# Main.net
KiCad netlist of a schematic drawn in Altium Designer
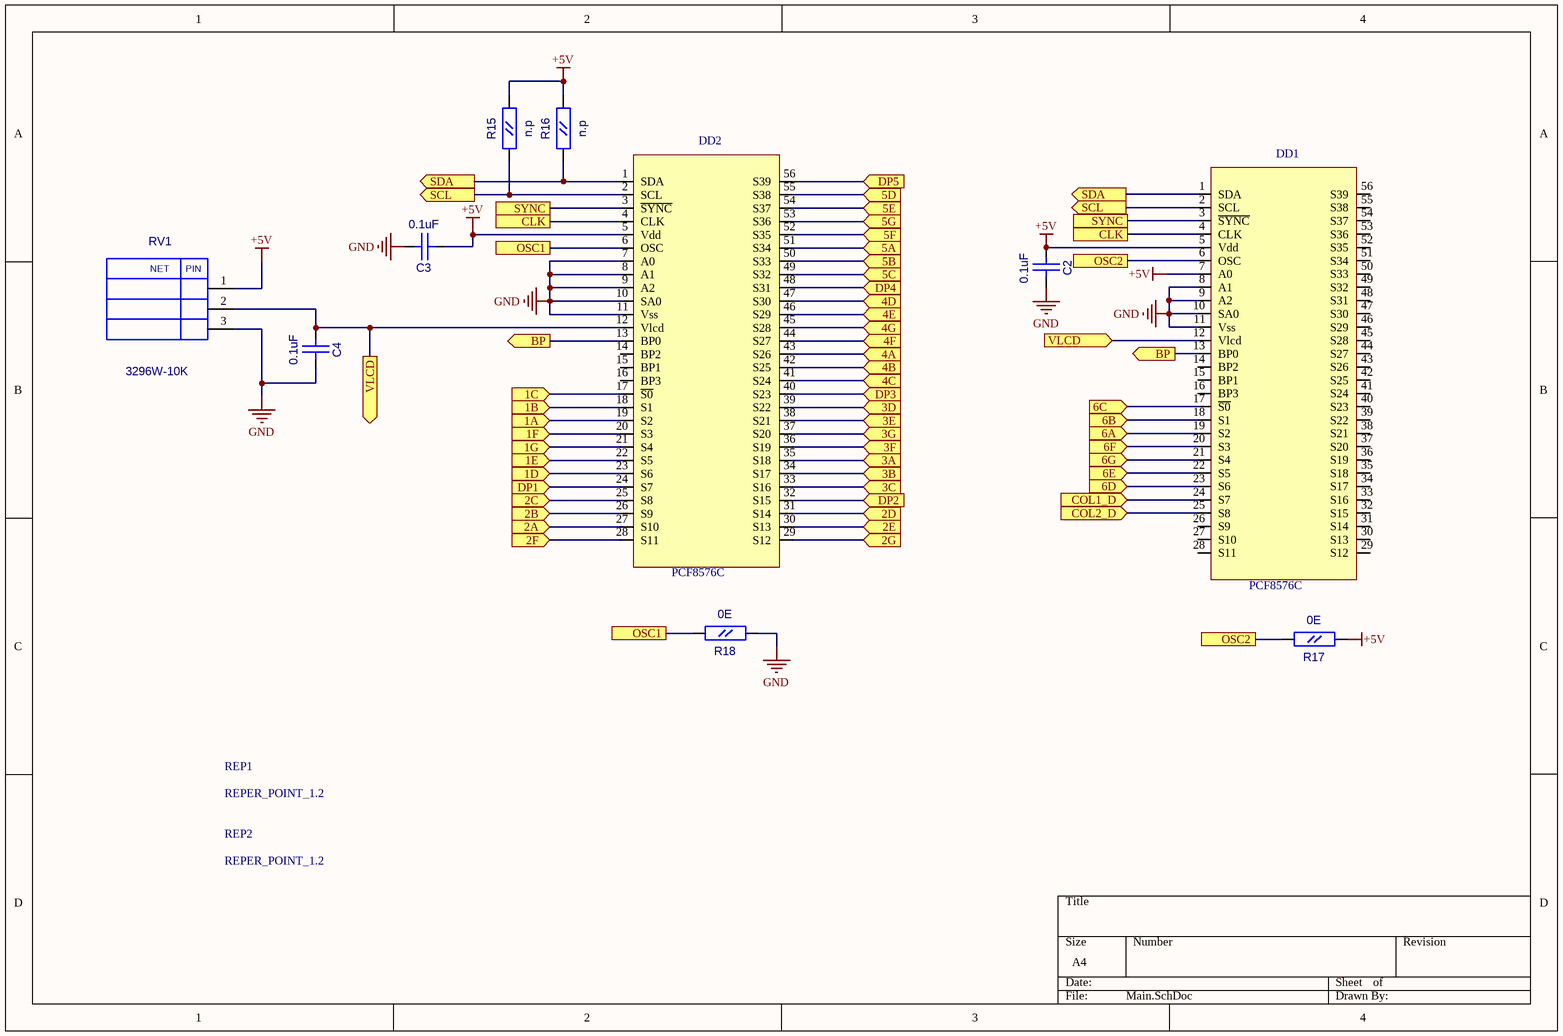
[diagram p0: Main.SchDoc]

(export (version "E")
  (design (tool "Eeschema 10.0.6"))
  (components
    (comp (ref "C2")
      (value "0.1uF")
      (footprint "CC0603")
      (description "CC0603")
      (libsource (lib "gprs_modem_2") (part "CC0603"))
    )
    (comp (ref "C3")
      (value "0.1uF")
      (footprint "CC0603")
      (description "CC0603")
      (libsource (lib "gprs_modem_2") (part "CC0603"))
    )
    (comp (ref "C4")
      (value "0.1uF")
      (footprint "CC0603")
      (description "CC0603")
      (libsource (lib "gprs_modem_2") (part "CC0603"))
    )
    (comp (ref "DD1")
      (value "PCF8576C")
      (footprint "SOT190-1")
      (description "LCD Controller")
      (libsource (lib "gprs_modem_2") (part "PCF8576"))
    )
    (comp (ref "DD2")
      (value "PCF8576C")
      (footprint "SOT190-1")
      (description "LCD Controller")
      (libsource (lib "gprs_modem_2") (part "PCF8576"))
    )
    (comp (ref "R15")
      (value "n.p")
      (footprint "RC0603")
      (description "RC0603")
      (libsource (lib "gprs_modem_2") (part "RC0603"))
    )
    (comp (ref "R16")
      (value "n.p")
      (footprint "RC0603")
      (description "RC0603")
      (libsource (lib "gprs_modem_2") (part "RC0603"))
    )
    (comp (ref "R17")
      (value "0E")
      (footprint "RC0603")
      (description "RC0603")
      (libsource (lib "gprs_modem_2") (part "RC0603"))
    )
    (comp (ref "R18")
      (value "0E")
      (footprint "RC0603")
      (description "RC0603")
      (libsource (lib "gprs_modem_2") (part "RC0603"))
    )
    (comp (ref "REP1")
      (value "REPER_POINT_1.2")
      (footprint "REPER1.2")
      (description "REPER1.2")
      (libsource (lib "gprs_modem_2") (part "REPER1.2"))
    )
    (comp (ref "REP2")
      (value "REPER_POINT_1.2")
      (footprint "REPER1.2")
      (description "REPER1.2")
      (libsource (lib "gprs_modem_2") (part "REPER1.2"))
    )
    (comp (ref "RV1")
      (value "3296W-10K")
      (footprint "PLS-03")
      (libsource (lib "gprs_modem_2") (part "PLS03"))
    )
  )
  (nets
    (net (code "1") (name "+5V") (class "Default")
      (node (ref "C2") (pin "1") (pinfunction "A_1") (pintype "passive"))
      (node (ref "C3") (pin "1") (pinfunction "A_1") (pintype "passive"))
      (node (ref "DD1") (pin "5") (pinfunction "Vdd_5") (pintype "passive"))
      (node (ref "DD1") (pin "7") (pinfunction "A0_7") (pintype "passive"))
      (node (ref "DD2") (pin "5") (pinfunction "Vdd_5") (pintype "passive"))
      (node (ref "R15") (pin "2") (pinfunction "B_2") (pintype "passive"))
      (node (ref "R16") (pin "2") (pinfunction "B_2") (pintype "passive"))
      (node (ref "R17") (pin "1") (pinfunction "A_1") (pintype "passive"))
      (node (ref "RV1") (pin "1") (pinfunction "1_1") (pintype "passive"))
    )
    (net (code "2") (name "/1A") (class "Default")
      (node (ref "DD2") (pin "19") (pinfunction "S2_19") (pintype "passive"))
    )
    (net (code "3") (name "/1B") (class "Default")
      (node (ref "DD2") (pin "18") (pinfunction "S1_18") (pintype "passive"))
    )
    (net (code "4") (name "/1C") (class "Default")
      (node (ref "DD2") (pin "17") (pinfunction "S0_17") (pintype "passive"))
    )
    (net (code "5") (name "/1D") (class "Default")
      (node (ref "DD2") (pin "23") (pinfunction "S6_23") (pintype "passive"))
    )
    (net (code "6") (name "/1E") (class "Default")
      (node (ref "DD2") (pin "22") (pinfunction "S5_22") (pintype "passive"))
    )
    (net (code "7") (name "/1F") (class "Default")
      (node (ref "DD2") (pin "20") (pinfunction "S3_20") (pintype "passive"))
    )
    (net (code "8") (name "/1G") (class "Default")
      (node (ref "DD2") (pin "21") (pinfunction "S4_21") (pintype "passive"))
    )
    (net (code "9") (name "/2A") (class "Default")
      (node (ref "DD2") (pin "27") (pinfunction "S10_27") (pintype "passive"))
    )
    (net (code "10") (name "/2B") (class "Default")
      (node (ref "DD2") (pin "26") (pinfunction "S9_26") (pintype "passive"))
    )
    (net (code "11") (name "/2C") (class "Default")
      (node (ref "DD2") (pin "25") (pinfunction "S8_25") (pintype "passive"))
    )
    (net (code "12") (name "/2D") (class "Default")
      (node (ref "DD2") (pin "31") (pinfunction "S14_31") (pintype "passive"))
    )
    (net (code "13") (name "/2E") (class "Default")
      (node (ref "DD2") (pin "30") (pinfunction "S13_30") (pintype "passive"))
    )
    (net (code "14") (name "/2F") (class "Default")
      (node (ref "DD2") (pin "28") (pinfunction "S11_28") (pintype "passive"))
    )
    (net (code "15") (name "/2G") (class "Default")
      (node (ref "DD2") (pin "29") (pinfunction "S12_29") (pintype "passive"))
    )
    (net (code "16") (name "/3A") (class "Default")
      (node (ref "DD2") (pin "35") (pinfunction "S18_35") (pintype "passive"))
    )
    (net (code "17") (name "/3B") (class "Default")
      (node (ref "DD2") (pin "34") (pinfunction "S17_34") (pintype "passive"))
    )
    (net (code "18") (name "/3C") (class "Default")
      (node (ref "DD2") (pin "33") (pinfunction "S16_33") (pintype "passive"))
    )
    (net (code "19") (name "/3D") (class "Default")
      (node (ref "DD2") (pin "39") (pinfunction "S22_39") (pintype "passive"))
    )
    (net (code "20") (name "/3E") (class "Default")
      (node (ref "DD2") (pin "38") (pinfunction "S21_38") (pintype "passive"))
    )
    (net (code "21") (name "/3F") (class "Default")
      (node (ref "DD2") (pin "36") (pinfunction "S19_36") (pintype "passive"))
    )
    (net (code "22") (name "/3G") (class "Default")
      (node (ref "DD2") (pin "37") (pinfunction "S20_37") (pintype "passive"))
    )
    (net (code "23") (name "/4A") (class "Default")
      (node (ref "DD2") (pin "43") (pinfunction "S26_43") (pintype "passive"))
    )
    (net (code "24") (name "/4B") (class "Default")
      (node (ref "DD2") (pin "42") (pinfunction "S25_42") (pintype "passive"))
    )
    (net (code "25") (name "/4C") (class "Default")
      (node (ref "DD2") (pin "41") (pinfunction "S24_41") (pintype "passive"))
    )
    (net (code "26") (name "/4D") (class "Default")
      (node (ref "DD2") (pin "47") (pinfunction "S30_47") (pintype "passive"))
    )
    (net (code "27") (name "/4E") (class "Default")
      (node (ref "DD2") (pin "46") (pinfunction "S29_46") (pintype "passive"))
    )
    (net (code "28") (name "/4F") (class "Default")
      (node (ref "DD2") (pin "44") (pinfunction "S27_44") (pintype "passive"))
    )
    (net (code "29") (name "/4G") (class "Default")
      (node (ref "DD2") (pin "45") (pinfunction "S28_45") (pintype "passive"))
    )
    (net (code "30") (name "/5A") (class "Default")
      (node (ref "DD2") (pin "51") (pinfunction "S34_51") (pintype "passive"))
    )
    (net (code "31") (name "/5B") (class "Default")
      (node (ref "DD2") (pin "50") (pinfunction "S33_50") (pintype "passive"))
    )
    (net (code "32") (name "/5C") (class "Default")
      (node (ref "DD2") (pin "49") (pinfunction "S32_49") (pintype "passive"))
    )
    (net (code "33") (name "/5D") (class "Default")
      (node (ref "DD2") (pin "55") (pinfunction "S38_55") (pintype "passive"))
    )
    (net (code "34") (name "/5E") (class "Default")
      (node (ref "DD2") (pin "54") (pinfunction "S37_54") (pintype "passive"))
    )
    (net (code "35") (name "/5F") (class "Default")
      (node (ref "DD2") (pin "52") (pinfunction "S35_52") (pintype "passive"))
    )
    (net (code "36") (name "/5G") (class "Default")
      (node (ref "DD2") (pin "53") (pinfunction "S36_53") (pintype "passive"))
    )
    (net (code "37") (name "/6A") (class "Default")
      (node (ref "DD1") (pin "19") (pinfunction "S2_19") (pintype "passive"))
    )
    (net (code "38") (name "/6B") (class "Default")
      (node (ref "DD1") (pin "18") (pinfunction "S1_18") (pintype "passive"))
    )
    (net (code "39") (name "/6C") (class "Default")
      (node (ref "DD1") (pin "17") (pinfunction "S0_17") (pintype "passive"))
    )
    (net (code "40") (name "/6D") (class "Default")
      (node (ref "DD1") (pin "23") (pinfunction "S6_23") (pintype "passive"))
    )
    (net (code "41") (name "/6E") (class "Default")
      (node (ref "DD1") (pin "22") (pinfunction "S5_22") (pintype "passive"))
    )
    (net (code "42") (name "/6F") (class "Default")
      (node (ref "DD1") (pin "20") (pinfunction "S3_20") (pintype "passive"))
    )
    (net (code "43") (name "/6G") (class "Default")
      (node (ref "DD1") (pin "21") (pinfunction "S4_21") (pintype "passive"))
    )
    (net (code "44") (name "/BP") (class "Default")
      (node (ref "DD1") (pin "13") (pinfunction "BP0_13") (pintype "passive"))
      (node (ref "DD2") (pin "13") (pinfunction "BP0_13") (pintype "passive"))
    )
    (net (code "45") (name "/CLK") (class "Default")
      (node (ref "DD1") (pin "4") (pinfunction "CLK_4") (pintype "passive"))
      (node (ref "DD2") (pin "4") (pinfunction "CLK_4") (pintype "passive"))
    )
    (net (code "46") (name "/COL1_D") (class "Default")
      (node (ref "DD1") (pin "24") (pinfunction "S7_24") (pintype "passive"))
    )
    (net (code "47") (name "/COL2_D") (class "Default")
      (node (ref "DD1") (pin "25") (pinfunction "S8_25") (pintype "passive"))
    )
    (net (code "48") (name "/DP1") (class "Default")
      (node (ref "DD2") (pin "24") (pinfunction "S7_24") (pintype "passive"))
    )
    (net (code "49") (name "/DP2") (class "Default")
      (node (ref "DD2") (pin "32") (pinfunction "S15_32") (pintype "passive"))
    )
    (net (code "50") (name "/DP3") (class "Default")
      (node (ref "DD2") (pin "40") (pinfunction "S23_40") (pintype "passive"))
    )
    (net (code "51") (name "/DP4") (class "Default")
      (node (ref "DD2") (pin "48") (pinfunction "S31_48") (pintype "passive"))
    )
    (net (code "52") (name "/DP5") (class "Default")
      (node (ref "DD2") (pin "56") (pinfunction "S39_56") (pintype "passive"))
    )
    (net (code "53") (name "/OSC1") (class "Default")
      (node (ref "DD2") (pin "6") (pinfunction "OSC_6") (pintype "passive"))
      (node (ref "R18") (pin "2") (pinfunction "B_2") (pintype "passive"))
    )
    (net (code "54") (name "/OSC2") (class "Default")
      (node (ref "DD1") (pin "6") (pinfunction "OSC_6") (pintype "passive"))
      (node (ref "R17") (pin "2") (pinfunction "B_2") (pintype "passive"))
    )
    (net (code "55") (name "/SCL") (class "Default")
      (node (ref "DD1") (pin "2") (pinfunction "SCL_2") (pintype "passive"))
      (node (ref "DD2") (pin "2") (pinfunction "SCL_2") (pintype "passive"))
      (node (ref "R15") (pin "1") (pinfunction "A_1") (pintype "passive"))
    )
    (net (code "56") (name "/SDA") (class "Default")
      (node (ref "DD1") (pin "1") (pinfunction "SDA_1") (pintype "passive"))
      (node (ref "DD2") (pin "1") (pinfunction "SDA_1") (pintype "passive"))
      (node (ref "R16") (pin "1") (pinfunction "A_1") (pintype "passive"))
    )
    (net (code "57") (name "/SYNC") (class "Default")
      (node (ref "DD1") (pin "3") (pinfunction "~{SYNC}_3") (pintype "passive"))
      (node (ref "DD2") (pin "3") (pinfunction "~{SYNC}_3") (pintype "passive"))
    )
    (net (code "58") (name "/VLCD") (class "Default")
      (node (ref "C4") (pin "1") (pinfunction "A_1") (pintype "passive"))
      (node (ref "DD1") (pin "12") (pinfunction "Vlcd_12") (pintype "passive"))
      (node (ref "DD2") (pin "12") (pinfunction "Vlcd_12") (pintype "passive"))
      (node (ref "RV1") (pin "2") (pinfunction "2_2") (pintype "passive"))
    )
    (net (code "59") (name "GND") (class "Default")
      (node (ref "C2") (pin "2") (pinfunction "B_2") (pintype "passive"))
      (node (ref "C3") (pin "2") (pinfunction "B_2") (pintype "passive"))
      (node (ref "C4") (pin "2") (pinfunction "B_2") (pintype "passive"))
      (node (ref "DD1") (pin "10") (pinfunction "SA0_10") (pintype "passive"))
      (node (ref "DD1") (pin "11") (pinfunction "Vss_11") (pintype "passive"))
      (node (ref "DD1") (pin "8") (pinfunction "A1_8") (pintype "passive"))
      (node (ref "DD1") (pin "9") (pinfunction "A2_9") (pintype "passive"))
      (node (ref "DD2") (pin "10") (pinfunction "SA0_10") (pintype "passive"))
      (node (ref "DD2") (pin "11") (pinfunction "Vss_11") (pintype "passive"))
      (node (ref "DD2") (pin "7") (pinfunction "A0_7") (pintype "passive"))
      (node (ref "DD2") (pin "8") (pinfunction "A1_8") (pintype "passive"))
      (node (ref "DD2") (pin "9") (pinfunction "A2_9") (pintype "passive"))
      (node (ref "R18") (pin "1") (pinfunction "A_1") (pintype "passive"))
      (node (ref "RV1") (pin "3") (pinfunction "3_3") (pintype "passive"))
    )
    (net (code "60") (name "unconnected-(DD1-BP1-Pad15)") (class "Default")
      (node (ref "DD1") (pin "15") (pinfunction "BP1_15") (pintype "passive"))
    )
    (net (code "61") (name "unconnected-(DD1-BP2-Pad14)") (class "Default")
      (node (ref "DD1") (pin "14") (pinfunction "BP2_14") (pintype "passive"))
    )
    (net (code "62") (name "unconnected-(DD1-BP3-Pad16)") (class "Default")
      (node (ref "DD1") (pin "16") (pinfunction "BP3_16") (pintype "passive"))
    )
    (net (code "63") (name "unconnected-(DD1-S9-Pad26)") (class "Default")
      (node (ref "DD1") (pin "26") (pinfunction "S9_26") (pintype "passive"))
    )
    (net (code "64") (name "unconnected-(DD1-S10-Pad27)") (class "Default")
      (node (ref "DD1") (pin "27") (pinfunction "S10_27") (pintype "passive"))
    )
    (net (code "65") (name "unconnected-(DD1-S11-Pad28)") (class "Default")
      (node (ref "DD1") (pin "28") (pinfunction "S11_28") (pintype "passive"))
    )
    (net (code "66") (name "unconnected-(DD1-S12-Pad29)") (class "Default")
      (node (ref "DD1") (pin "29") (pinfunction "S12_29") (pintype "passive"))
    )
    (net (code "67") (name "unconnected-(DD1-S13-Pad30)") (class "Default")
      (node (ref "DD1") (pin "30") (pinfunction "S13_30") (pintype "passive"))
    )
    (net (code "68") (name "unconnected-(DD1-S14-Pad31)") (class "Default")
      (node (ref "DD1") (pin "31") (pinfunction "S14_31") (pintype "passive"))
    )
    (net (code "69") (name "unconnected-(DD1-S15-Pad32)") (class "Default")
      (node (ref "DD1") (pin "32") (pinfunction "S15_32") (pintype "passive"))
    )
    (net (code "70") (name "unconnected-(DD1-S16-Pad33)") (class "Default")
      (node (ref "DD1") (pin "33") (pinfunction "S16_33") (pintype "passive"))
    )
    (net (code "71") (name "unconnected-(DD1-S17-Pad34)") (class "Default")
      (node (ref "DD1") (pin "34") (pinfunction "S17_34") (pintype "passive"))
    )
    (net (code "72") (name "unconnected-(DD1-S18-Pad35)") (class "Default")
      (node (ref "DD1") (pin "35") (pinfunction "S18_35") (pintype "passive"))
    )
    (net (code "73") (name "unconnected-(DD1-S19-Pad36)") (class "Default")
      (node (ref "DD1") (pin "36") (pinfunction "S19_36") (pintype "passive"))
    )
    (net (code "74") (name "unconnected-(DD1-S20-Pad37)") (class "Default")
      (node (ref "DD1") (pin "37") (pinfunction "S20_37") (pintype "passive"))
    )
    (net (code "75") (name "unconnected-(DD1-S21-Pad38)") (class "Default")
      (node (ref "DD1") (pin "38") (pinfunction "S21_38") (pintype "passive"))
    )
    (net (code "76") (name "unconnected-(DD1-S22-Pad39)") (class "Default")
      (node (ref "DD1") (pin "39") (pinfunction "S22_39") (pintype "passive"))
    )
    (net (code "77") (name "unconnected-(DD1-S23-Pad40)") (class "Default")
      (node (ref "DD1") (pin "40") (pinfunction "S23_40") (pintype "passive"))
    )
    (net (code "78") (name "unconnected-(DD1-S24-Pad41)") (class "Default")
      (node (ref "DD1") (pin "41") (pinfunction "S24_41") (pintype "passive"))
    )
    (net (code "79") (name "unconnected-(DD1-S25-Pad42)") (class "Default")
      (node (ref "DD1") (pin "42") (pinfunction "S25_42") (pintype "passive"))
    )
    (net (code "80") (name "unconnected-(DD1-S26-Pad43)") (class "Default")
      (node (ref "DD1") (pin "43") (pinfunction "S26_43") (pintype "passive"))
    )
    (net (code "81") (name "unconnected-(DD1-S27-Pad44)") (class "Default")
      (node (ref "DD1") (pin "44") (pinfunction "S27_44") (pintype "passive"))
    )
    (net (code "82") (name "unconnected-(DD1-S28-Pad45)") (class "Default")
      (node (ref "DD1") (pin "45") (pinfunction "S28_45") (pintype "passive"))
    )
    (net (code "83") (name "unconnected-(DD1-S29-Pad46)") (class "Default")
      (node (ref "DD1") (pin "46") (pinfunction "S29_46") (pintype "passive"))
    )
    (net (code "84") (name "unconnected-(DD1-S30-Pad47)") (class "Default")
      (node (ref "DD1") (pin "47") (pinfunction "S30_47") (pintype "passive"))
    )
    (net (code "85") (name "unconnected-(DD1-S31-Pad48)") (class "Default")
      (node (ref "DD1") (pin "48") (pinfunction "S31_48") (pintype "passive"))
    )
    (net (code "86") (name "unconnected-(DD1-S32-Pad49)") (class "Default")
      (node (ref "DD1") (pin "49") (pinfunction "S32_49") (pintype "passive"))
    )
    (net (code "87") (name "unconnected-(DD1-S33-Pad50)") (class "Default")
      (node (ref "DD1") (pin "50") (pinfunction "S33_50") (pintype "passive"))
    )
    (net (code "88") (name "unconnected-(DD1-S34-Pad51)") (class "Default")
      (node (ref "DD1") (pin "51") (pinfunction "S34_51") (pintype "passive"))
    )
    (net (code "89") (name "unconnected-(DD1-S35-Pad52)") (class "Default")
      (node (ref "DD1") (pin "52") (pinfunction "S35_52") (pintype "passive"))
    )
    (net (code "90") (name "unconnected-(DD1-S36-Pad53)") (class "Default")
      (node (ref "DD1") (pin "53") (pinfunction "S36_53") (pintype "passive"))
    )
    (net (code "91") (name "unconnected-(DD1-S37-Pad54)") (class "Default")
      (node (ref "DD1") (pin "54") (pinfunction "S37_54") (pintype "passive"))
    )
    (net (code "92") (name "unconnected-(DD1-S38-Pad55)") (class "Default")
      (node (ref "DD1") (pin "55") (pinfunction "S38_55") (pintype "passive"))
    )
    (net (code "93") (name "unconnected-(DD1-S39-Pad56)") (class "Default")
      (node (ref "DD1") (pin "56") (pinfunction "S39_56") (pintype "passive"))
    )
    (net (code "94") (name "unconnected-(DD2-BP1-Pad15)") (class "Default")
      (node (ref "DD2") (pin "15") (pinfunction "BP1_15") (pintype "passive"))
    )
    (net (code "95") (name "unconnected-(DD2-BP2-Pad14)") (class "Default")
      (node (ref "DD2") (pin "14") (pinfunction "BP2_14") (pintype "passive"))
    )
    (net (code "96") (name "unconnected-(DD2-BP3-Pad16)") (class "Default")
      (node (ref "DD2") (pin "16") (pinfunction "BP3_16") (pintype "passive"))
    )
    (net (code "97") (name "unconnected-(REP1-Pad1)") (class "Default")
      (node (ref "REP1") (pin "1") (pintype "passive"))
    )
    (net (code "98") (name "unconnected-(REP2-Pad1)") (class "Default")
      (node (ref "REP2") (pin "1") (pintype "passive"))
    )
  )
)
